# v1.net
KiCad netlist of a schematic drawn in EAGLE
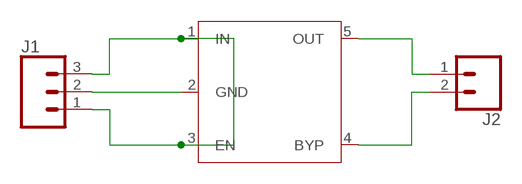
[diagram p0: schematic, sheet 1]

(export (version "E")
  (design (tool "Eeschema 10.0.6"))
  (components
    (comp (ref "J1")
      (value "CONN_03")
      (footprint "eagle-import:1X03")
      (libsource (lib "eagle-import") (part "CONN_03"))
    )
    (comp (ref "J2")
      (value "CONN_02")
      (footprint "eagle-import:1X02")
      (libsource (lib "eagle-import") (part "CONN_02"))
    )
    (comp (ref "U$1")
      (value "MIC5219")
      (footprint "eagle-import:SOT95P280X145-5N")
      (libsource (lib "eagle-import") (part "MIC5219"))
    )
  )
  (nets
    (net (code "1") (name "Net-(U$1-BYP)") (class "Default")
      (node (ref "J2") (pin "2") (pinfunction "2_2") (pintype "passive"))
      (node (ref "U$1") (pin "4") (pinfunction "BYP_4") (pintype "bidirectional"))
    )
    (net (code "2") (name "Net-(U$1-EN)") (class "Default")
      (node (ref "J1") (pin "1") (pinfunction "1_1") (pintype "passive"))
      (node (ref "J1") (pin "3") (pinfunction "3_3") (pintype "passive"))
      (node (ref "U$1") (pin "1") (pinfunction "IN_1") (pintype "bidirectional"))
      (node (ref "U$1") (pin "3") (pinfunction "EN_3") (pintype "bidirectional"))
    )
    (net (code "3") (name "Net-(U$1-GND)") (class "Default")
      (node (ref "J1") (pin "2") (pinfunction "2_2") (pintype "passive"))
      (node (ref "U$1") (pin "2") (pinfunction "GND_2") (pintype "bidirectional"))
    )
    (net (code "4") (name "Net-(U$1-OUT)") (class "Default")
      (node (ref "J2") (pin "1") (pinfunction "1_1") (pintype "passive"))
      (node (ref "U$1") (pin "5") (pinfunction "OUT_5") (pintype "bidirectional"))
    )
  )
)
